# Port_F_Output_Port.net
KiCad netlist of a schematic drawn in Altium Designer
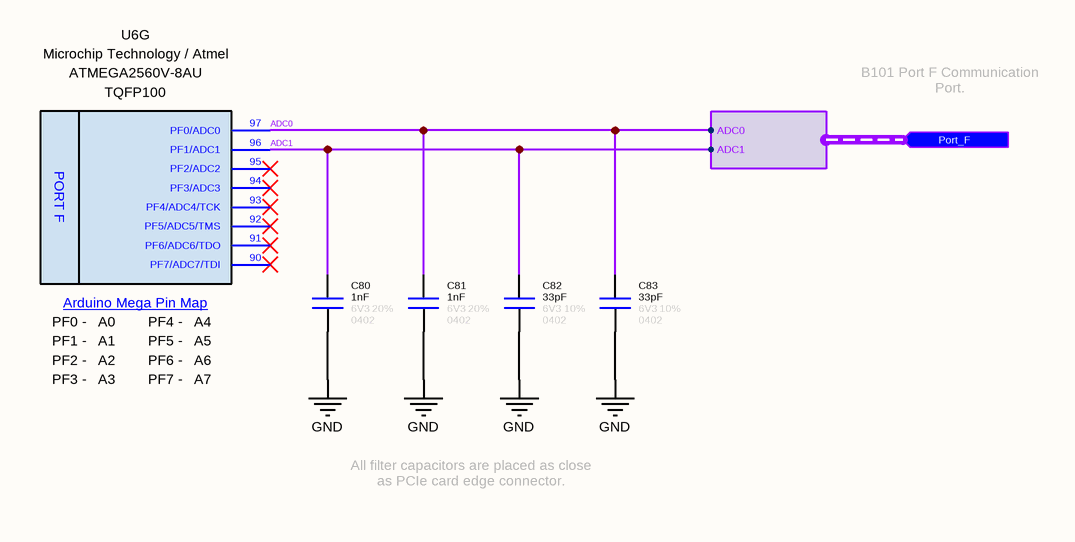
[diagram p0: Port F Output Port.SchDoc]

(export (version "E")
  (design (tool "Eeschema 10.0.6"))
  (components
    (comp (ref "C80")
      (value "1nF")
      (footprint "CAPACITOR_0402")
      (description "Capacitor - 1nF [0402] (Ceramic)")
      (fields
        (field (name "MANUFACTURER PART NUMBER") "04026C102MAT2A")
        (field (name "TOLERANCE") "20%")
        (field (name "CASE") "0402")
        (field (name "VOLTAGE") "6V3")
      )
      (libsource (lib "P101DA_Library") (part "Capacitor - 1nF [0402-6V3]"))
    )
    (comp (ref "C81")
      (value "1nF")
      (footprint "CAPACITOR_0402")
      (description "Capacitor - 1nF [0402] (Ceramic)")
      (fields
        (field (name "MANUFACTURER PART NUMBER") "04026C102MAT2A")
        (field (name "TOLERANCE") "20%")
        (field (name "CASE") "0402")
        (field (name "VOLTAGE") "6V3")
      )
      (libsource (lib "P101DA_Library") (part "Capacitor - 1nF [0402-6V3]"))
    )
    (comp (ref "C82")
      (value "33pF")
      (footprint "CAPACITOR_0402")
      (description "Capacitor - 33pF [0402] (Ceramic)")
      (fields
        (field (name "MANUFACTURER PART NUMBER") "C0402C330J9RACAUTO")
        (field (name "TOLERANCE") "10%")
        (field (name "CASE") "0402")
        (field (name "VOLTAGE") "6V3")
      )
      (libsource (lib "P101DA_Library") (part "Capacitor - 33pF [0402-6V3]"))
    )
    (comp (ref "C83")
      (value "33pF")
      (footprint "CAPACITOR_0402")
      (description "Capacitor - 33pF [0402] (Ceramic)")
      (fields
        (field (name "MANUFACTURER PART NUMBER") "C0402C330J9RACAUTO")
        (field (name "TOLERANCE") "10%")
        (field (name "CASE") "0402")
        (field (name "VOLTAGE") "6V3")
      )
      (libsource (lib "P101DA_Library") (part "Capacitor - 33pF [0402-6V3]"))
    )
    (comp (ref "U6")
      (value "ATMEGA2560V-8AU")
      (footprint "TQFP-100")
      (description "ATmega Series 256 KB Flash 8 KB SRAM 8 MHz 8-Bit Microcontroller - TQFP-100")
      (fields
        (field (name "MANUFACTURER NAME") "Microchip Technology / Atmel")
        (field (name "MANUFACTURER PART NUMBER") "ATMEGA2560V-8AU")
        (field (name "CASE") "TQFP100")
      )
      (libsource (lib "P101DA_Library") (part "IC - AtMega2560V-8AU"))
    )
  )
  (nets
    (net (code "2") (name "/ADC0") (class "Default")
      (node (ref "C81") (pin "2") (pinfunction "2_2") (pintype "passive"))
      (node (ref "C83") (pin "2") (pinfunction "2_2") (pintype "passive"))
      (node (ref "U6") (pin "97") (pinfunction "PF0/ADC0_97") (pintype "passive"))
    )
    (net (code "3") (name "/ADC1") (class "Default")
      (node (ref "C80") (pin "2") (pinfunction "2_2") (pintype "passive"))
      (node (ref "C82") (pin "2") (pinfunction "2_2") (pintype "passive"))
      (node (ref "U6") (pin "96") (pinfunction "PF1/ADC1_96") (pintype "passive"))
    )
    (net (code "5") (name "GND") (class "Default")
      (node (ref "C80") (pin "1") (pinfunction "1_1") (pintype "passive"))
      (node (ref "C81") (pin "1") (pinfunction "1_1") (pintype "passive"))
      (node (ref "C82") (pin "1") (pinfunction "1_1") (pintype "passive"))
      (node (ref "C83") (pin "1") (pinfunction "1_1") (pintype "passive"))
    )
    (net (code "6") (name "unconnected-(U6G-PF2{slash}ADC2-Pad95)") (class "Default")
      (node (ref "U6") (pin "95") (pinfunction "PF2/ADC2_95") (pintype "passive+no_connect"))
    )
    (net (code "7") (name "unconnected-(U6G-PF3{slash}ADC3-Pad94)") (class "Default")
      (node (ref "U6") (pin "94") (pinfunction "PF3/ADC3_94") (pintype "passive+no_connect"))
    )
    (net (code "8") (name "unconnected-(U6G-PF4{slash}ADC4{slash}TCK-Pad93)") (class "Default")
      (node (ref "U6") (pin "93") (pinfunction "PF4/ADC4/TCK_93") (pintype "passive+no_connect"))
    )
    (net (code "9") (name "unconnected-(U6G-PF5{slash}ADC5{slash}TMS-Pad92)") (class "Default")
      (node (ref "U6") (pin "92") (pinfunction "PF5/ADC5/TMS_92") (pintype "passive+no_connect"))
    )
    (net (code "10") (name "unconnected-(U6G-PF6{slash}ADC6{slash}TDO-Pad91)") (class "Default")
      (node (ref "U6") (pin "91") (pinfunction "PF6/ADC6/TDO_91") (pintype "passive+no_connect"))
    )
    (net (code "11") (name "unconnected-(U6G-PF7{slash}ADC7{slash}TDI-Pad90)") (class "Default")
      (node (ref "U6") (pin "90") (pinfunction "PF7/ADC7/TDI_90") (pintype "passive+no_connect"))
    )
  )
)
